# stim.net
KiCad netlist of a schematic drawn in EAGLE
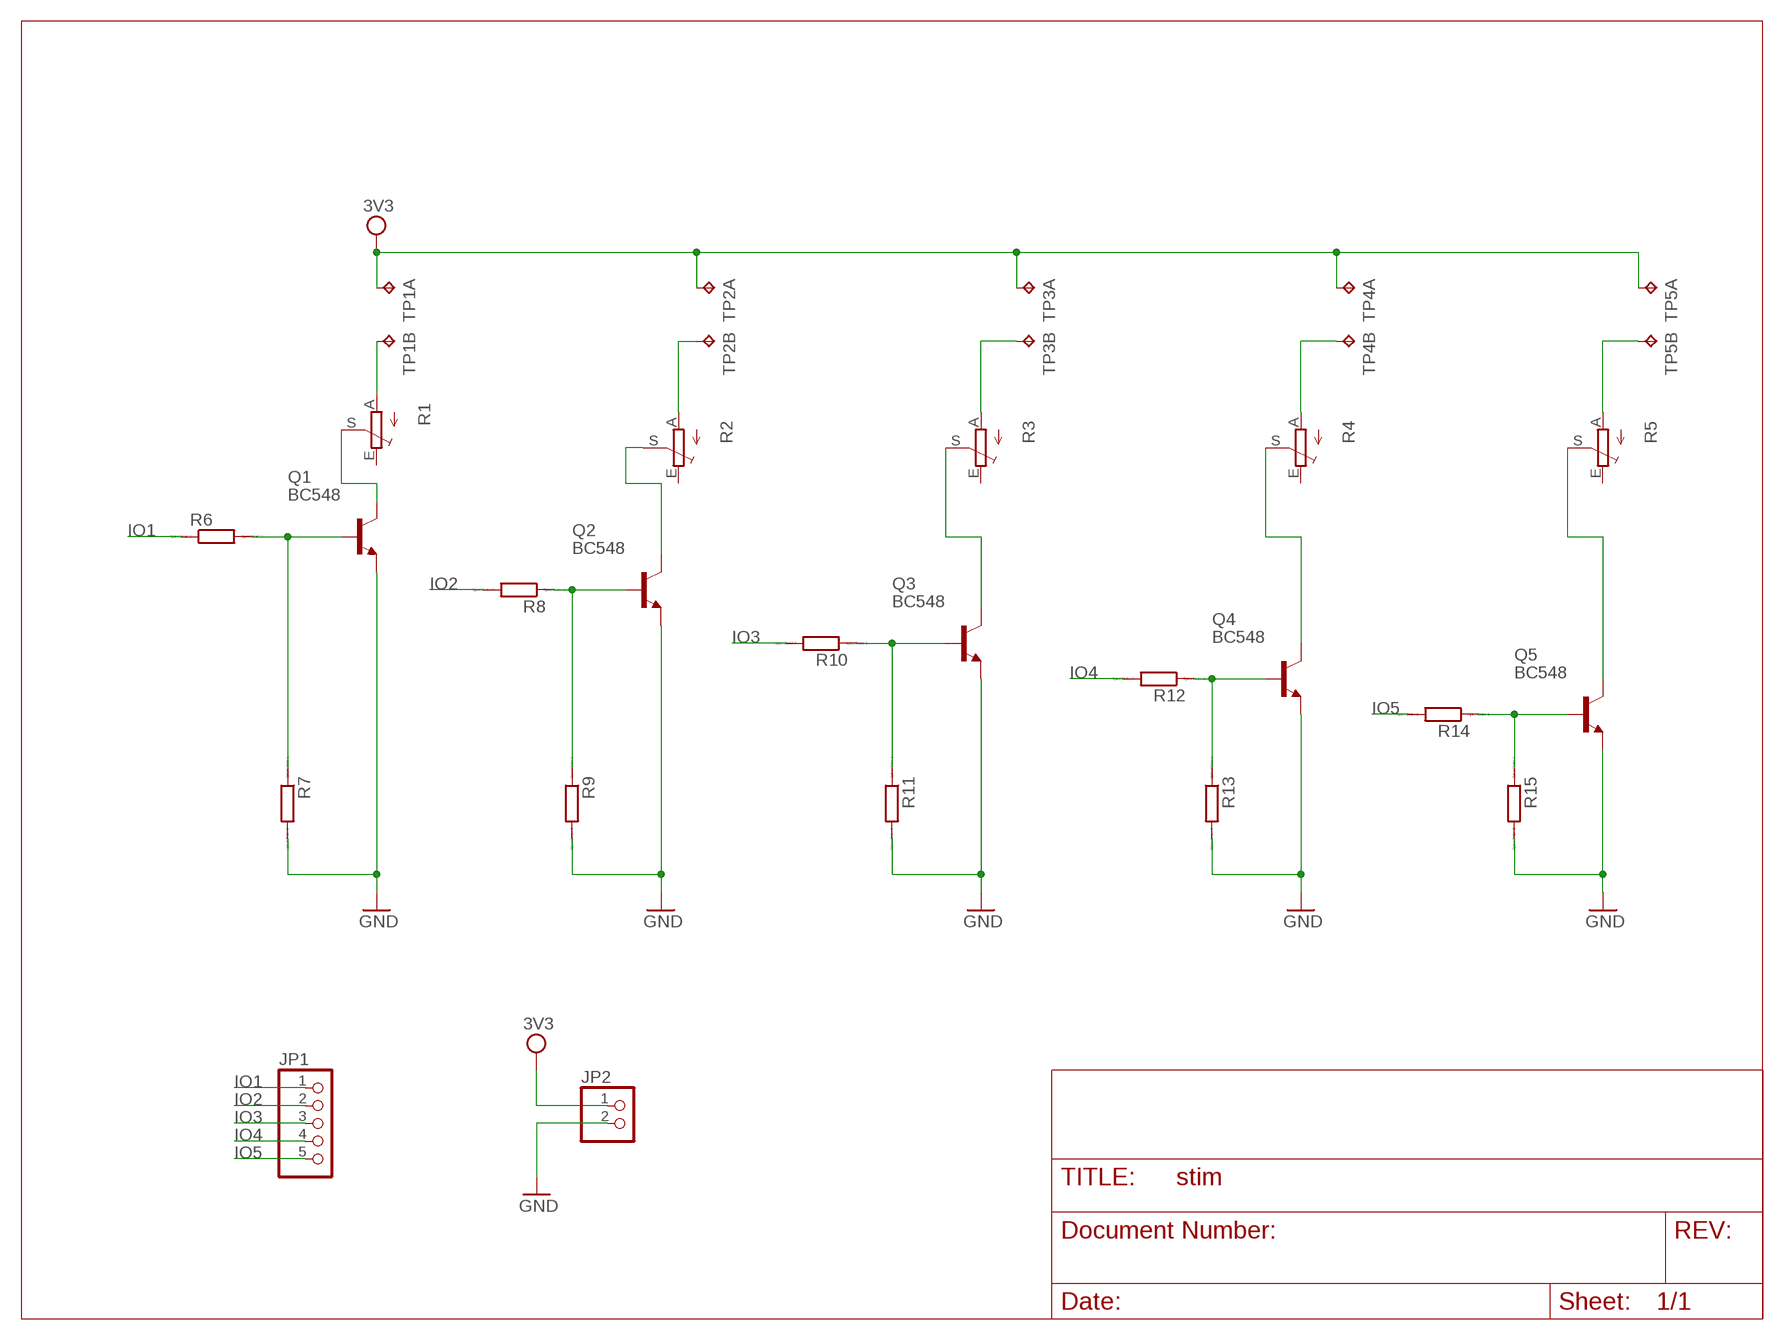
[diagram p0: schematic, sheet 1]

(export (version "E")
  (design (tool "Eeschema 10.0.6"))
  (components
    (comp (ref "JP1")
      (value "PINHD-1X5")
      (footprint "eagle-import:1X05")
      (libsource (lib "eagle-import") (part "PINHD-1X5"))
    )
    (comp (ref "JP2")
      (value "PINHD-1X2")
      (footprint "eagle-import:1X02")
      (libsource (lib "eagle-import") (part "PINHD-1X2"))
    )
    (comp (ref "Q1")
      (value "BC548")
      (footprint "eagle-import:TO92-EBC")
      (libsource (lib "eagle-import") (part "BC548"))
    )
    (comp (ref "Q2")
      (value "BC548")
      (footprint "eagle-import:TO92-EBC")
      (libsource (lib "eagle-import") (part "BC548"))
    )
    (comp (ref "Q3")
      (value "BC548")
      (footprint "eagle-import:TO92-EBC")
      (libsource (lib "eagle-import") (part "BC548"))
    )
    (comp (ref "Q4")
      (value "BC548")
      (footprint "eagle-import:TO92-EBC")
      (libsource (lib "eagle-import") (part "BC548"))
    )
    (comp (ref "Q5")
      (value "BC548")
      (footprint "eagle-import:TO92-EBC")
      (libsource (lib "eagle-import") (part "BC548"))
    )
    (comp (ref "R1")
      (value "TRIM_EU-B25V")
      (footprint "eagle-import:B25V")
      (libsource (lib "eagle-import") (part "TRIM_EU-B25V"))
    )
    (comp (ref "R2")
      (value "TRIM_EU-B25V")
      (footprint "eagle-import:B25V")
      (libsource (lib "eagle-import") (part "TRIM_EU-B25V"))
    )
    (comp (ref "R3")
      (value "TRIM_EU-B25V")
      (footprint "eagle-import:B25V")
      (libsource (lib "eagle-import") (part "TRIM_EU-B25V"))
    )
    (comp (ref "R4")
      (value "TRIM_EU-B25V")
      (footprint "eagle-import:B25V")
      (libsource (lib "eagle-import") (part "TRIM_EU-B25V"))
    )
    (comp (ref "R5")
      (value "TRIM_EU-B25V")
      (footprint "eagle-import:B25V")
      (libsource (lib "eagle-import") (part "TRIM_EU-B25V"))
    )
    (comp (ref "R6")
      (value "RR1206")
      (footprint "eagle-import:R1206")
      (libsource (lib "eagle-import") (part "RR1206"))
    )
    (comp (ref "R7")
      (value "RR1206")
      (footprint "eagle-import:R1206")
      (libsource (lib "eagle-import") (part "RR1206"))
    )
    (comp (ref "R8")
      (value "RR1206")
      (footprint "eagle-import:R1206")
      (libsource (lib "eagle-import") (part "RR1206"))
    )
    (comp (ref "R9")
      (value "RR1206")
      (footprint "eagle-import:R1206")
      (libsource (lib "eagle-import") (part "RR1206"))
    )
    (comp (ref "R10")
      (value "RR1206")
      (footprint "eagle-import:R1206")
      (libsource (lib "eagle-import") (part "RR1206"))
    )
    (comp (ref "R11")
      (value "RR1206")
      (footprint "eagle-import:R1206")
      (libsource (lib "eagle-import") (part "RR1206"))
    )
    (comp (ref "R12")
      (value "RR1206")
      (footprint "eagle-import:R1206")
      (libsource (lib "eagle-import") (part "RR1206"))
    )
    (comp (ref "R13")
      (value "RR1206")
      (footprint "eagle-import:R1206")
      (libsource (lib "eagle-import") (part "RR1206"))
    )
    (comp (ref "R14")
      (value "RR1206")
      (footprint "eagle-import:R1206")
      (libsource (lib "eagle-import") (part "RR1206"))
    )
    (comp (ref "R15")
      (value "RR1206")
      (footprint "eagle-import:R1206")
      (libsource (lib "eagle-import") (part "RR1206"))
    )
    (comp (ref "TP1")
      (value "TP2P2-38-17")
      (footprint "eagle-import:P2-38-17")
      (libsource (lib "eagle-import") (part "TP2P2-38-17"))
    )
    (comp (ref "TP2")
      (value "TP2P2-38-17")
      (footprint "eagle-import:P2-38-17")
      (libsource (lib "eagle-import") (part "TP2P2-38-17"))
    )
    (comp (ref "TP3")
      (value "TP2P2-38-17")
      (footprint "eagle-import:P2-38-17")
      (libsource (lib "eagle-import") (part "TP2P2-38-17"))
    )
    (comp (ref "TP4")
      (value "TP2P2-38-17")
      (footprint "eagle-import:P2-38-17")
      (libsource (lib "eagle-import") (part "TP2P2-38-17"))
    )
    (comp (ref "TP5")
      (value "TP2P2-38-17")
      (footprint "eagle-import:P2-38-17")
      (libsource (lib "eagle-import") (part "TP2P2-38-17"))
    )
  )
  (nets
    (net (code "1") (name "/IO1") (class "Default")
      (node (ref "JP1") (pin "1") (pinfunction "1_1") (pintype "passive"))
      (node (ref "R6") (pin "1") (pinfunction "1_1") (pintype "passive"))
    )
    (net (code "2") (name "/IO2") (class "Default")
      (node (ref "JP1") (pin "2") (pinfunction "2_2") (pintype "passive"))
      (node (ref "R8") (pin "2") (pinfunction "2_2") (pintype "passive"))
    )
    (net (code "3") (name "/IO3") (class "Default")
      (node (ref "JP1") (pin "3") (pinfunction "3_3") (pintype "passive"))
      (node (ref "R10") (pin "2") (pinfunction "2_2") (pintype "passive"))
    )
    (net (code "4") (name "/IO4") (class "Default")
      (node (ref "JP1") (pin "4") (pinfunction "4_4") (pintype "passive"))
      (node (ref "R12") (pin "2") (pinfunction "2_2") (pintype "passive"))
    )
    (net (code "5") (name "/IO5") (class "Default")
      (node (ref "JP1") (pin "5") (pinfunction "5_5") (pintype "passive"))
      (node (ref "R14") (pin "2") (pinfunction "2_2") (pintype "passive"))
    )
    (net (code "6") (name "3V3") (class "Default")
      (node (ref "JP2") (pin "1") (pinfunction "1_1") (pintype "passive"))
      (node (ref "TP1") (pin "TP-1") (pinfunction "TP_TP-1") (pintype "input"))
      (node (ref "TP2") (pin "TP-1") (pinfunction "TP_TP-1") (pintype "input"))
      (node (ref "TP3") (pin "TP-1") (pinfunction "TP_TP-1") (pintype "input"))
      (node (ref "TP4") (pin "TP-1") (pinfunction "TP_TP-1") (pintype "input"))
      (node (ref "TP5") (pin "TP-1") (pinfunction "TP_TP-1") (pintype "input"))
    )
    (net (code "7") (name "GND") (class "Default")
      (node (ref "JP2") (pin "2") (pinfunction "2_2") (pintype "passive"))
      (node (ref "Q1") (pin "E") (pinfunction "E_E") (pintype "passive"))
      (node (ref "Q2") (pin "E") (pinfunction "E_E") (pintype "passive"))
      (node (ref "Q3") (pin "E") (pinfunction "E_E") (pintype "passive"))
      (node (ref "Q4") (pin "E") (pinfunction "E_E") (pintype "passive"))
      (node (ref "Q5") (pin "E") (pinfunction "E_E") (pintype "passive"))
      (node (ref "R11") (pin "2") (pinfunction "2_2") (pintype "passive"))
      (node (ref "R13") (pin "2") (pinfunction "2_2") (pintype "passive"))
      (node (ref "R15") (pin "2") (pinfunction "2_2") (pintype "passive"))
      (node (ref "R7") (pin "2") (pinfunction "2_2") (pintype "passive"))
      (node (ref "R9") (pin "2") (pinfunction "2_2") (pintype "passive"))
    )
    (net (code "8") (name "Net-(Q1-PadB)") (class "Default")
      (node (ref "Q1") (pin "B") (pinfunction "B_B") (pintype "passive"))
      (node (ref "R6") (pin "2") (pinfunction "2_2") (pintype "passive"))
      (node (ref "R7") (pin "1") (pinfunction "1_1") (pintype "passive"))
    )
    (net (code "9") (name "Net-(Q1-PadC)") (class "Default")
      (node (ref "Q1") (pin "C") (pinfunction "C_C") (pintype "passive"))
      (node (ref "R1") (pin "S") (pinfunction "S_S") (pintype "passive"))
    )
    (net (code "10") (name "Net-(Q2-PadB)") (class "Default")
      (node (ref "Q2") (pin "B") (pinfunction "B_B") (pintype "passive"))
      (node (ref "R8") (pin "1") (pinfunction "1_1") (pintype "passive"))
      (node (ref "R9") (pin "1") (pinfunction "1_1") (pintype "passive"))
    )
    (net (code "11") (name "Net-(Q2-PadC)") (class "Default")
      (node (ref "Q2") (pin "C") (pinfunction "C_C") (pintype "passive"))
      (node (ref "R2") (pin "S") (pinfunction "S_S") (pintype "passive"))
    )
    (net (code "12") (name "Net-(Q3-PadB)") (class "Default")
      (node (ref "Q3") (pin "B") (pinfunction "B_B") (pintype "passive"))
      (node (ref "R10") (pin "1") (pinfunction "1_1") (pintype "passive"))
      (node (ref "R11") (pin "1") (pinfunction "1_1") (pintype "passive"))
    )
    (net (code "13") (name "Net-(Q3-PadC)") (class "Default")
      (node (ref "Q3") (pin "C") (pinfunction "C_C") (pintype "passive"))
      (node (ref "R3") (pin "S") (pinfunction "S_S") (pintype "passive"))
    )
    (net (code "14") (name "Net-(Q4-PadB)") (class "Default")
      (node (ref "Q4") (pin "B") (pinfunction "B_B") (pintype "passive"))
      (node (ref "R12") (pin "1") (pinfunction "1_1") (pintype "passive"))
      (node (ref "R13") (pin "1") (pinfunction "1_1") (pintype "passive"))
    )
    (net (code "15") (name "Net-(Q4-PadC)") (class "Default")
      (node (ref "Q4") (pin "C") (pinfunction "C_C") (pintype "passive"))
      (node (ref "R4") (pin "S") (pinfunction "S_S") (pintype "passive"))
    )
    (net (code "16") (name "Net-(Q5-PadB)") (class "Default")
      (node (ref "Q5") (pin "B") (pinfunction "B_B") (pintype "passive"))
      (node (ref "R14") (pin "1") (pinfunction "1_1") (pintype "passive"))
      (node (ref "R15") (pin "1") (pinfunction "1_1") (pintype "passive"))
    )
    (net (code "17") (name "Net-(Q5-PadC)") (class "Default")
      (node (ref "Q5") (pin "C") (pinfunction "C_C") (pintype "passive"))
      (node (ref "R5") (pin "S") (pinfunction "S_S") (pintype "passive"))
    )
    (net (code "18") (name "Net-(TP1B-TP)") (class "Default")
      (node (ref "R1") (pin "A") (pinfunction "A_A") (pintype "passive"))
      (node (ref "TP1") (pin "TP-2") (pinfunction "TP_TP-2") (pintype "input"))
    )
    (net (code "19") (name "Net-(TP2B-TP)") (class "Default")
      (node (ref "R2") (pin "A") (pinfunction "A_A") (pintype "passive"))
      (node (ref "TP2") (pin "TP-2") (pinfunction "TP_TP-2") (pintype "input"))
    )
    (net (code "20") (name "Net-(TP3B-TP)") (class "Default")
      (node (ref "R3") (pin "A") (pinfunction "A_A") (pintype "passive"))
      (node (ref "TP3") (pin "TP-2") (pinfunction "TP_TP-2") (pintype "input"))
    )
    (net (code "21") (name "Net-(TP4B-TP)") (class "Default")
      (node (ref "R4") (pin "A") (pinfunction "A_A") (pintype "passive"))
      (node (ref "TP4") (pin "TP-2") (pinfunction "TP_TP-2") (pintype "input"))
    )
    (net (code "22") (name "Net-(TP5B-TP)") (class "Default")
      (node (ref "R5") (pin "A") (pinfunction "A_A") (pintype "passive"))
      (node (ref "TP5") (pin "TP-2") (pinfunction "TP_TP-2") (pintype "input"))
    )
    (net (code "23") (name "unconnected-(R1-PadE)") (class "Default")
      (node (ref "R1") (pin "E") (pinfunction "E_E") (pintype "passive"))
    )
    (net (code "24") (name "unconnected-(R2-PadE)") (class "Default")
      (node (ref "R2") (pin "E") (pinfunction "E_E") (pintype "passive"))
    )
    (net (code "25") (name "unconnected-(R3-PadE)") (class "Default")
      (node (ref "R3") (pin "E") (pinfunction "E_E") (pintype "passive"))
    )
    (net (code "26") (name "unconnected-(R4-PadE)") (class "Default")
      (node (ref "R4") (pin "E") (pinfunction "E_E") (pintype "passive"))
    )
    (net (code "27") (name "unconnected-(R5-PadE)") (class "Default")
      (node (ref "R5") (pin "E") (pinfunction "E_E") (pintype "passive"))
    )
  )
)
